# teensy_dev_board.net
KiCad netlist of a schematic drawn in EAGLE
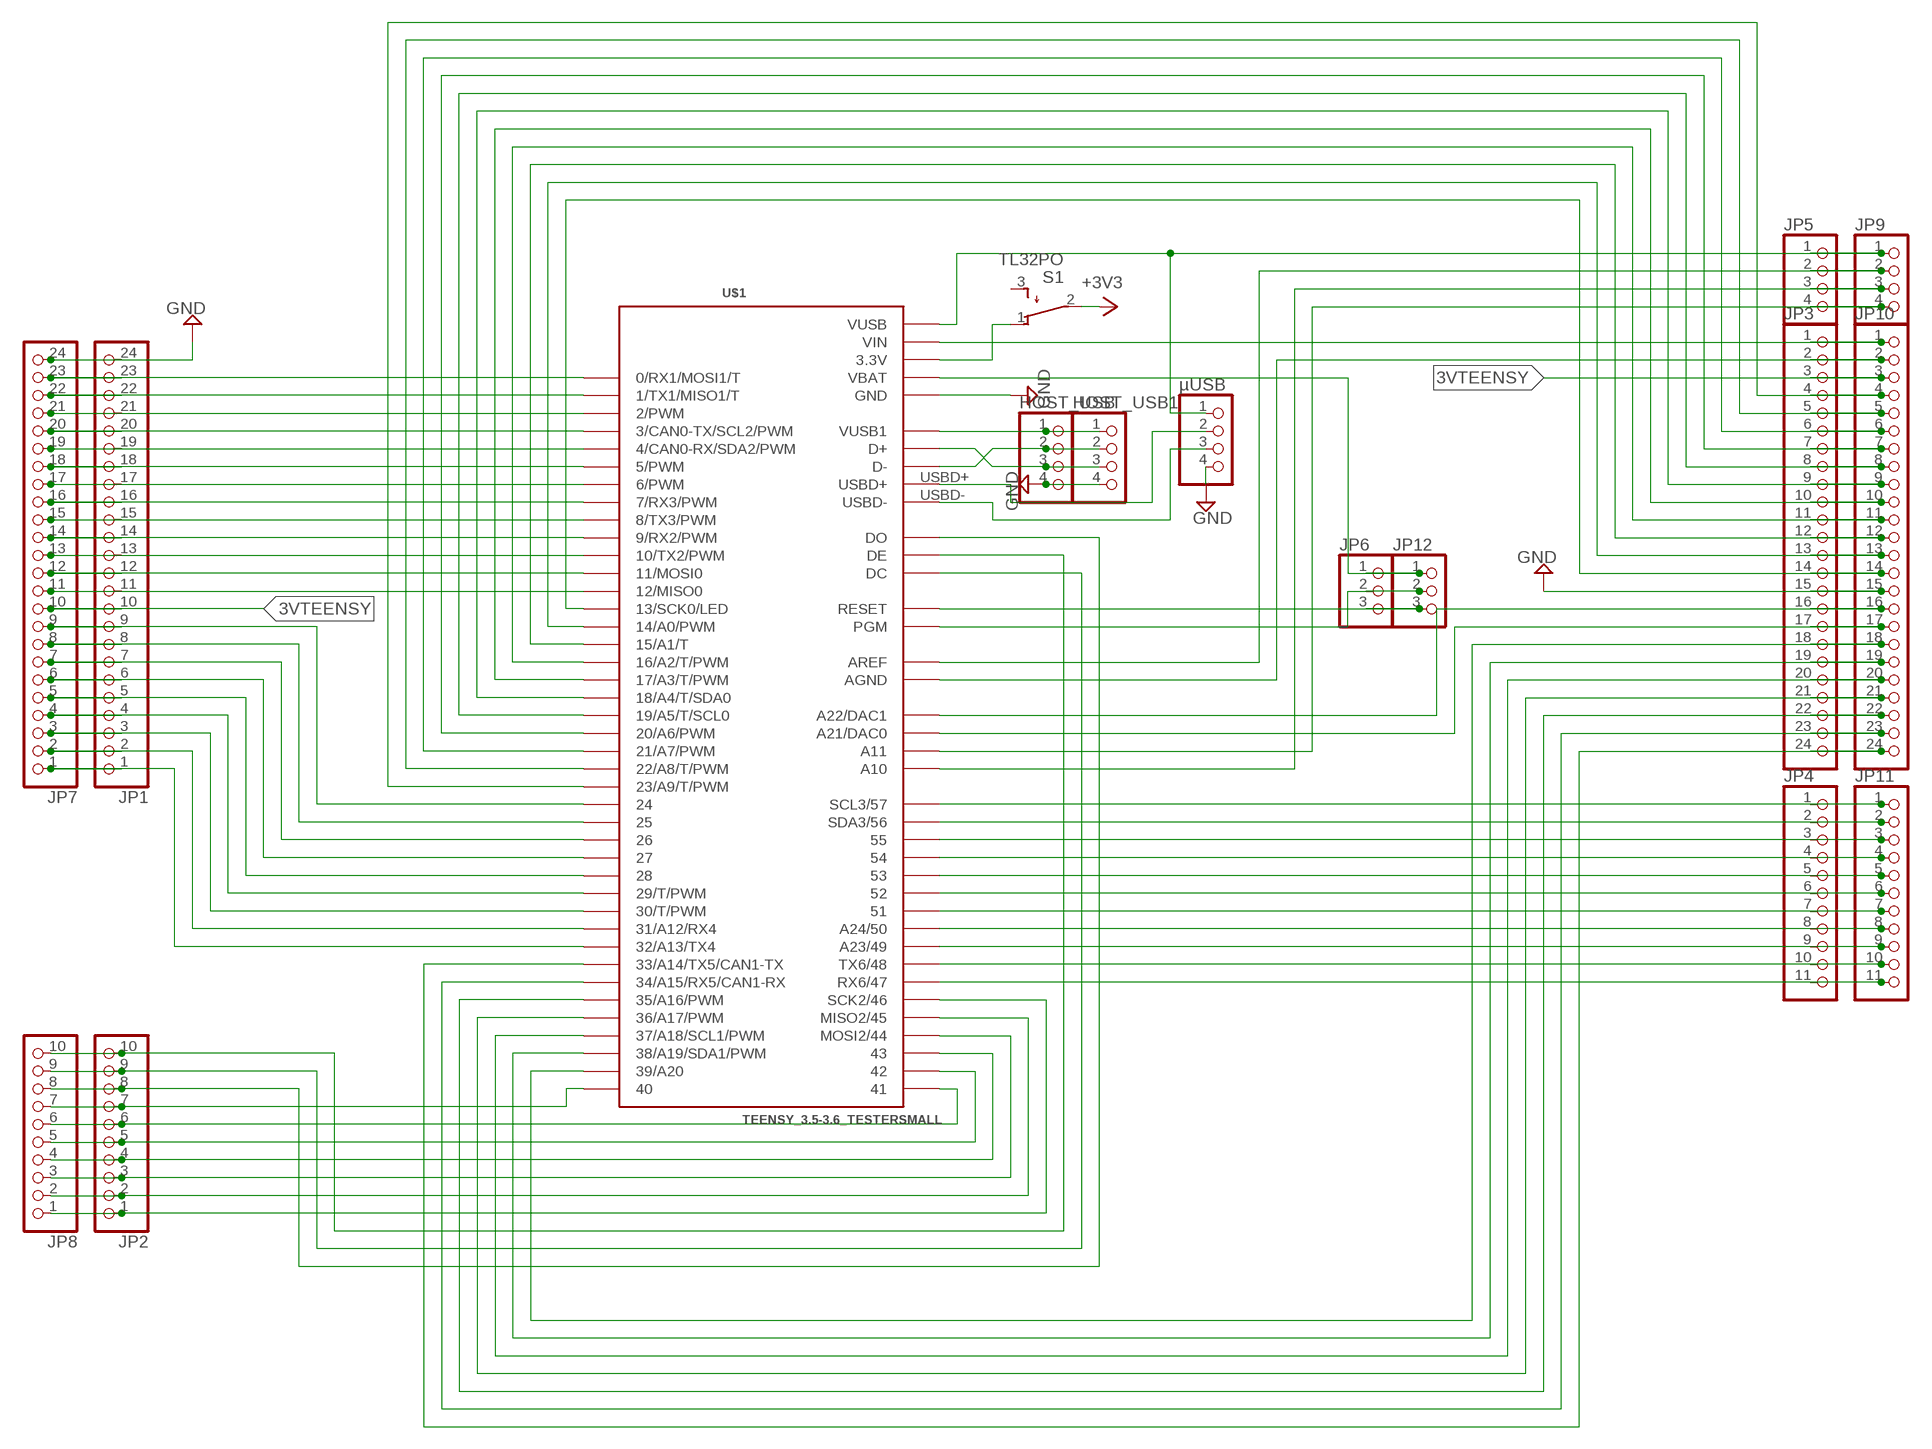
[diagram p0: schematic, sheet 1, part 1 of 2]
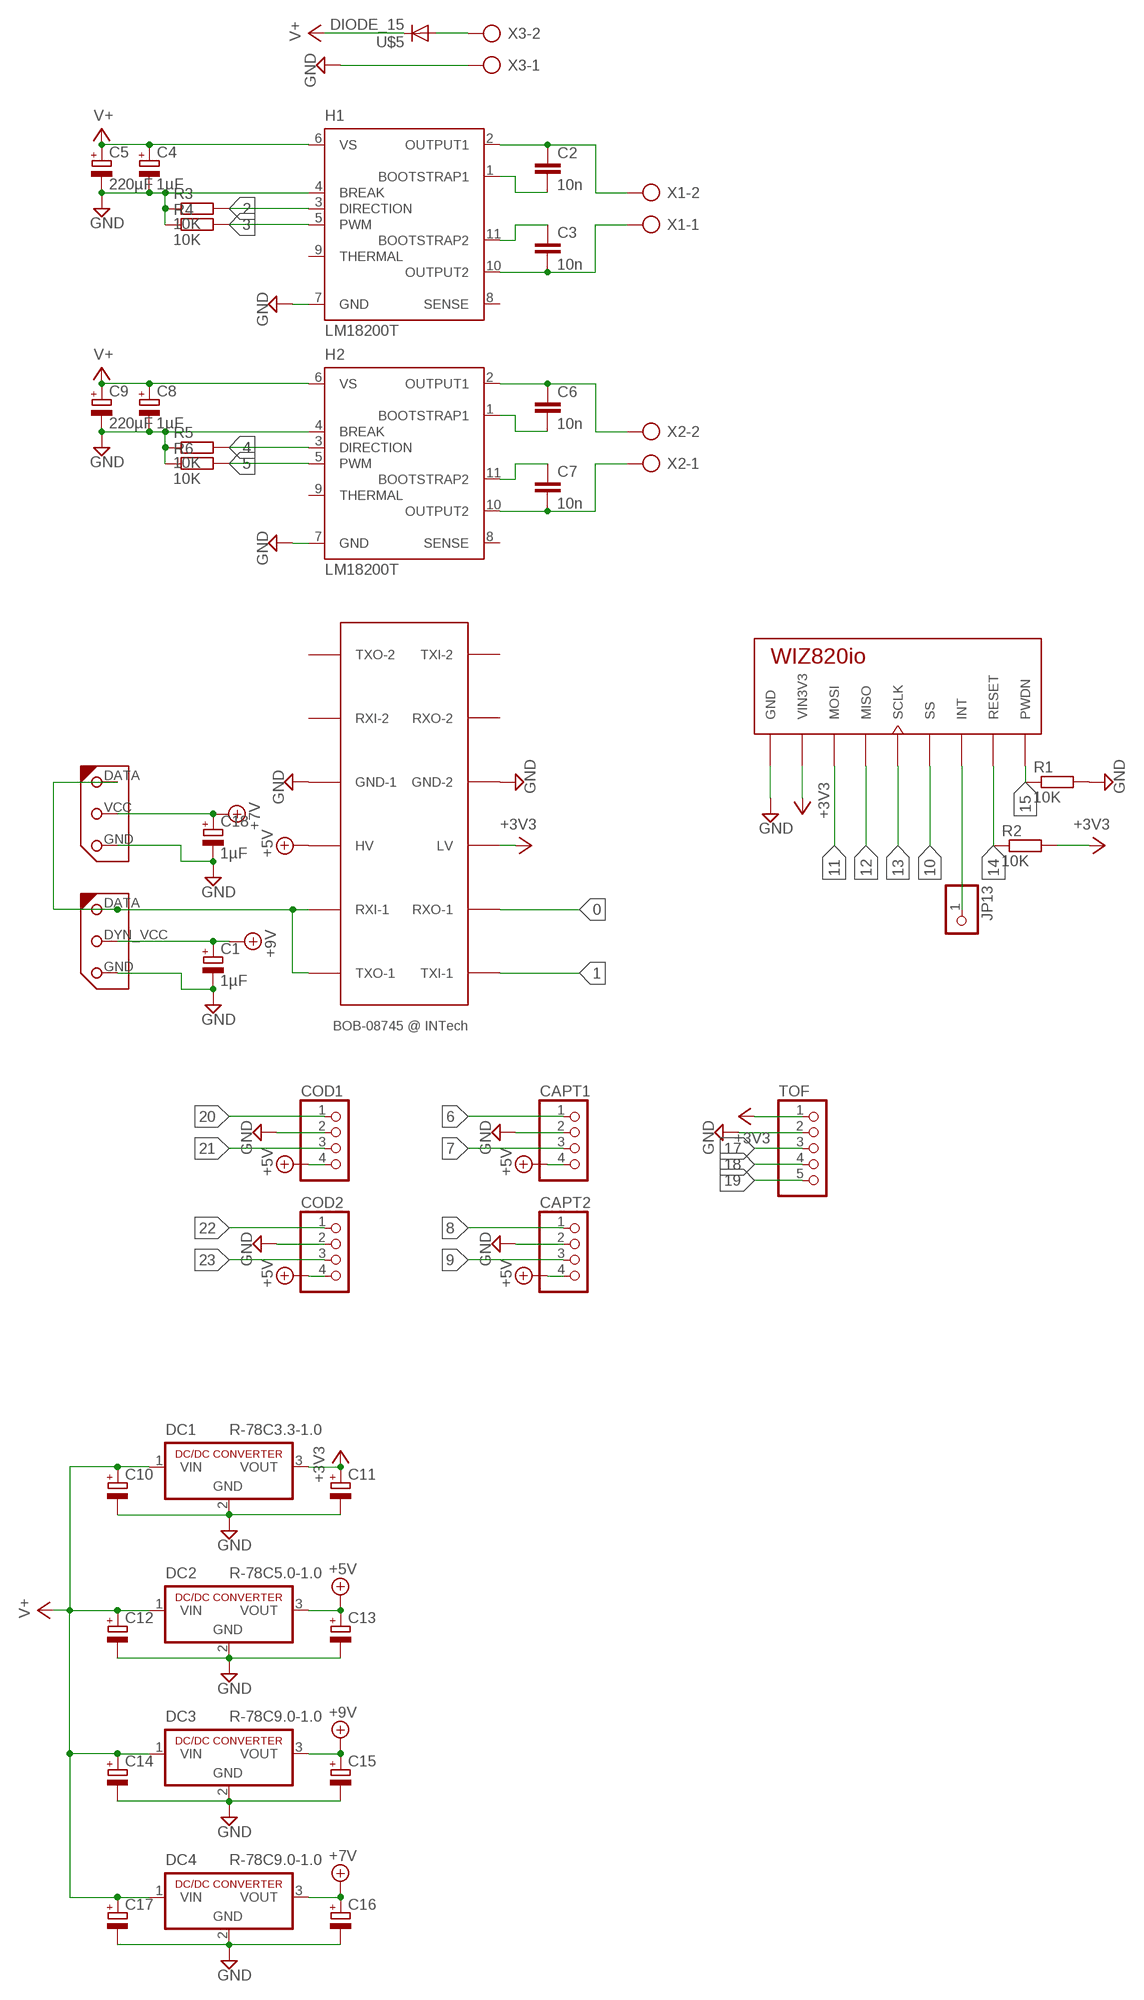
[diagram p1: schematic, sheet 1, part 2 of 2]

(export (version "E")
  (design (tool "Eeschema 10.0.6"))
  (components
    (comp (ref "C1")
      (value "1µF")
      (footprint "eagle-import:E2,5-6E")
      (libsource (lib "eagle-import") (part "CPOL-EUE2,5-6E"))
    )
    (comp (ref "C2")
      (value "10n")
      (footprint "eagle-import:C050-025X075")
      (libsource (lib "eagle-import") (part "C-EU050-025X075"))
    )
    (comp (ref "C3")
      (value "10n")
      (footprint "eagle-import:C050-025X075")
      (libsource (lib "eagle-import") (part "C-EU050-025X075"))
    )
    (comp (ref "C4")
      (value "1µF")
      (footprint "eagle-import:E2,5-7")
      (libsource (lib "eagle-import") (part "CPOL-EUE2.5-7"))
    )
    (comp (ref "C5")
      (value "220µF")
      (footprint "eagle-import:E2,5-7")
      (libsource (lib "eagle-import") (part "CPOL-EUE2.5-7"))
    )
    (comp (ref "C6")
      (value "10n")
      (footprint "eagle-import:C050-025X075")
      (libsource (lib "eagle-import") (part "C-EU050-025X075"))
    )
    (comp (ref "C7")
      (value "10n")
      (footprint "eagle-import:C050-025X075")
      (libsource (lib "eagle-import") (part "C-EU050-025X075"))
    )
    (comp (ref "C8")
      (value "1µF")
      (footprint "eagle-import:E2,5-7")
      (libsource (lib "eagle-import") (part "CPOL-EUE2.5-7"))
    )
    (comp (ref "C9")
      (value "220µF")
      (footprint "eagle-import:E2,5-7")
      (libsource (lib "eagle-import") (part "CPOL-EUE2.5-7"))
    )
    (comp (ref "C10")
      (value "CPOL-EUE2.5-6")
      (footprint "eagle-import:E2,5-6")
      (libsource (lib "eagle-import") (part "CPOL-EUE2.5-6"))
    )
    (comp (ref "C11")
      (value "CPOL-EUE2.5-6")
      (footprint "eagle-import:E2,5-6")
      (libsource (lib "eagle-import") (part "CPOL-EUE2.5-6"))
    )
    (comp (ref "C12")
      (value "CPOL-EUE2.5-6")
      (footprint "eagle-import:E2,5-6")
      (libsource (lib "eagle-import") (part "CPOL-EUE2.5-6"))
    )
    (comp (ref "C13")
      (value "CPOL-EUE2.5-6")
      (footprint "eagle-import:E2,5-6")
      (libsource (lib "eagle-import") (part "CPOL-EUE2.5-6"))
    )
    (comp (ref "C14")
      (value "CPOL-EUE2.5-6")
      (footprint "eagle-import:E2,5-6")
      (libsource (lib "eagle-import") (part "CPOL-EUE2.5-6"))
    )
    (comp (ref "C15")
      (value "CPOL-EUE2.5-6")
      (footprint "eagle-import:E2,5-6")
      (libsource (lib "eagle-import") (part "CPOL-EUE2.5-6"))
    )
    (comp (ref "C16")
      (value "CPOL-EUE2.5-6")
      (footprint "eagle-import:E2,5-6")
      (libsource (lib "eagle-import") (part "CPOL-EUE2.5-6"))
    )
    (comp (ref "C17")
      (value "CPOL-EUE2.5-6")
      (footprint "eagle-import:E2,5-6")
      (libsource (lib "eagle-import") (part "CPOL-EUE2.5-6"))
    )
    (comp (ref "C18")
      (value "1µF")
      (footprint "eagle-import:E2,5-6E")
      (libsource (lib "eagle-import") (part "CPOL-EUE2,5-6E"))
    )
    (comp (ref "CAPT1")
      (value "PINHD-1X4B")
      (footprint "eagle-import:1X04B")
      (libsource (lib "eagle-import") (part "PINHD-1X4B"))
    )
    (comp (ref "CAPT2")
      (value "PINHD-1X4B")
      (footprint "eagle-import:1X04B")
      (libsource (lib "eagle-import") (part "PINHD-1X4B"))
    )
    (comp (ref "COD1")
      (value "PINHD-1X4B")
      (footprint "eagle-import:1X04B")
      (libsource (lib "eagle-import") (part "PINHD-1X4B"))
    )
    (comp (ref "COD2")
      (value "PINHD-1X4B")
      (footprint "eagle-import:1X04B")
      (libsource (lib "eagle-import") (part "PINHD-1X4B"))
    )
    (comp (ref "DC1")
      (value "R-78C3.3-1.0")
      (footprint "eagle-import:SIP3")
      (libsource (lib "eagle-import") (part "R-78C-1.03.3"))
    )
    (comp (ref "DC2")
      (value "R-78C5.0-1.0")
      (footprint "eagle-import:SIP3")
      (libsource (lib "eagle-import") (part "R-78C-1.05.0"))
    )
    (comp (ref "DC3")
      (value "R-78C9.0-1.0")
      (footprint "eagle-import:SIP3")
      (libsource (lib "eagle-import") (part "R-78C-1.09.0"))
    )
    (comp (ref "DC4")
      (value "R-78C9.0-1.0")
      (footprint "eagle-import:SIP3")
      (libsource (lib "eagle-import") (part "R-78C-1.09.0"))
    )
    (comp (ref "H1")
      (value "LM18200T")
      (footprint "eagle-import:TO-220-11")
      (libsource (lib "eagle-import") (part "LM18200T"))
    )
    (comp (ref "H2")
      (value "LM18200T")
      (footprint "eagle-import:TO-220-11")
      (libsource (lib "eagle-import") (part "LM18200T"))
    )
    (comp (ref "HOST_USB")
      (value "PINHD-1X4")
      (footprint "eagle-import:1X04")
      (libsource (lib "eagle-import") (part "PINHD-1X4"))
    )
    (comp (ref "HOST_USB1")
      (value "PINHD-1X4")
      (footprint "eagle-import:1X04")
      (libsource (lib "eagle-import") (part "PINHD-1X4"))
    )
    (comp (ref "JP1")
      (value "PINHD-1X24")
      (footprint "eagle-import:1X24")
      (libsource (lib "eagle-import") (part "PINHD-1X24"))
    )
    (comp (ref "JP2")
      (value "PINHD-1X10")
      (footprint "eagle-import:1X10")
      (libsource (lib "eagle-import") (part "PINHD-1X10"))
    )
    (comp (ref "JP3")
      (value "PINHD-1X24")
      (footprint "eagle-import:1X24")
      (libsource (lib "eagle-import") (part "PINHD-1X24"))
    )
    (comp (ref "JP4")
      (value "PINHD-1X11")
      (footprint "eagle-import:1X11")
      (libsource (lib "eagle-import") (part "PINHD-1X11"))
    )
    (comp (ref "JP5")
      (value "PINHD-1X4")
      (footprint "eagle-import:1X04")
      (libsource (lib "eagle-import") (part "PINHD-1X4"))
    )
    (comp (ref "JP6")
      (value "PINHD-1X3")
      (footprint "eagle-import:1X03")
      (libsource (lib "eagle-import") (part "PINHD-1X3"))
    )
    (comp (ref "JP7")
      (value "PINHD-1X24")
      (footprint "eagle-import:1X24")
      (libsource (lib "eagle-import") (part "PINHD-1X24"))
    )
    (comp (ref "JP8")
      (value "PINHD-1X10")
      (footprint "eagle-import:1X10")
      (libsource (lib "eagle-import") (part "PINHD-1X10"))
    )
    (comp (ref "JP9")
      (value "PINHD-1X4")
      (footprint "eagle-import:1X04")
      (libsource (lib "eagle-import") (part "PINHD-1X4"))
    )
    (comp (ref "JP10")
      (value "PINHD-1X24")
      (footprint "eagle-import:1X24")
      (libsource (lib "eagle-import") (part "PINHD-1X24"))
    )
    (comp (ref "JP11")
      (value "PINHD-1X11")
      (footprint "eagle-import:1X11")
      (libsource (lib "eagle-import") (part "PINHD-1X11"))
    )
    (comp (ref "JP12")
      (value "PINHD-1X3")
      (footprint "eagle-import:1X03")
      (libsource (lib "eagle-import") (part "PINHD-1X3"))
    )
    (comp (ref "JP13")
      (value "PINHD-1X1")
      (footprint "eagle-import:1X01")
      (libsource (lib "eagle-import") (part "PINHD-1X1"))
    )
    (comp (ref "R1")
      (value "10K")
      (footprint "eagle-import:0204_7")
      (libsource (lib "eagle-import") (part "R-EU_0204/7"))
    )
    (comp (ref "R2")
      (value "10K")
      (footprint "eagle-import:0204_7")
      (libsource (lib "eagle-import") (part "R-EU_0204/7"))
    )
    (comp (ref "R3")
      (value "10K")
      (footprint "eagle-import:0204_7")
      (libsource (lib "eagle-import") (part "R-EU_0204/7"))
    )
    (comp (ref "R4")
      (value "10K")
      (footprint "eagle-import:0204_7")
      (libsource (lib "eagle-import") (part "R-EU_0204/7"))
    )
    (comp (ref "R5")
      (value "10K")
      (footprint "eagle-import:0204_7")
      (libsource (lib "eagle-import") (part "R-EU_0204/7"))
    )
    (comp (ref "R6")
      (value "10K")
      (footprint "eagle-import:0204_7")
      (libsource (lib "eagle-import") (part "R-EU_0204/7"))
    )
    (comp (ref "S1")
      (value "TL32PO")
      (footprint "eagle-import:TL3XPO")
      (libsource (lib "eagle-import") (part "TL32PO"))
    )
    (comp (ref "TOF")
      (value "PINHD-1X5B")
      (footprint "eagle-import:1X05B")
      (libsource (lib "eagle-import") (part "PINHD-1X5B"))
    )
    (comp (ref "U$1")
      (value "TEENSY_3.5-3.6_TESTERSMALL")
      (footprint "eagle-import:TEENSY_3.5-3.6_TESTER_SMALL")
      (libsource (lib "eagle-import") (part "TEENSY_3.5-3.6_TESTERSMALL"))
    )
    (comp (ref "U$2")
      (value "BOB-08745")
      (footprint "eagle-import:BOB-08745")
      (libsource (lib "eagle-import") (part "BOB-08745"))
    )
    (comp (ref "U$3")
      (value "DYNAMIXEL-1X03AX")
      (footprint "eagle-import:DYNAMIXEL_AX_1X03")
      (libsource (lib "eagle-import") (part "DYNAMIXEL-1X03AX"))
    )
    (comp (ref "U$4")
      (value "WIZ820IO")
      (footprint "eagle-import:WIZ820")
      (libsource (lib "eagle-import") (part "WIZ820IO"))
    )
    (comp (ref "U$5")
      (value "DIODE_15")
      (footprint "eagle-import:DO201-15")
      (libsource (lib "eagle-import") (part "DIODE_15"))
    )
    (comp (ref "U$6")
      (value "DYNAMIXEL-1X03XL")
      (footprint "eagle-import:DYNAMIXEL_XL_1X03")
      (libsource (lib "eagle-import") (part "DYNAMIXEL-1X03XL"))
    )
    (comp (ref "X1")
      (value "AK300/2")
      (footprint "eagle-import:AK300_2")
      (libsource (lib "eagle-import") (part "AK300/2"))
    )
    (comp (ref "X2")
      (value "AK300/2")
      (footprint "eagle-import:AK300_2")
      (libsource (lib "eagle-import") (part "AK300/2"))
    )
    (comp (ref "X3")
      (value "AK300/2")
      (footprint "eagle-import:AK300_2")
      (libsource (lib "eagle-import") (part "AK300/2"))
    )
    (comp (ref "µUSB")
      (value "PINHD-1X4")
      (footprint "eagle-import:1X04")
      (libsource (lib "eagle-import") (part "PINHD-1X4"))
    )
  )
  (nets
    (net (code "1") (name "+3V3") (class "Default")
      (node (ref "C11") (pin "+") (pinfunction "+_+") (pintype "passive"))
      (node (ref "DC1") (pin "3") (pinfunction "VOUT_3") (pintype "passive"))
      (node (ref "R2") (pin "2") (pinfunction "2_2") (pintype "passive"))
      (node (ref "S1") (pin "2") (pinfunction "P_2") (pintype "passive"))
      (node (ref "TOF") (pin "1") (pinfunction "1_1") (pintype "passive"))
      (node (ref "U$2") (pin "LV") (pinfunction "LV_LV") (pintype "bidirectional"))
      (node (ref "U$4") (pin "VIN1") (pinfunction "VIN3V3_VIN1") (pintype "power_in"))
      (node (ref "U$4") (pin "VIN2") (pinfunction "VIN3V3_VIN2") (pintype "power_in"))
    )
    (net (code "2") (name "+5V") (class "Default")
      (node (ref "C13") (pin "+") (pinfunction "+_+") (pintype "passive"))
      (node (ref "CAPT1") (pin "4") (pinfunction "4_4") (pintype "passive"))
      (node (ref "CAPT2") (pin "4") (pinfunction "4_4") (pintype "passive"))
      (node (ref "COD1") (pin "4") (pinfunction "4_4") (pintype "passive"))
      (node (ref "COD2") (pin "4") (pinfunction "4_4") (pintype "passive"))
      (node (ref "DC2") (pin "3") (pinfunction "VOUT_3") (pintype "passive"))
      (node (ref "U$2") (pin "HV") (pinfunction "HV_HV") (pintype "bidirectional"))
    )
    (net (code "3") (name "+7V") (class "Default")
      (node (ref "C16") (pin "+") (pinfunction "+_+") (pintype "passive"))
      (node (ref "C18") (pin "+") (pinfunction "+_+") (pintype "passive"))
      (node (ref "DC4") (pin "3") (pinfunction "VOUT_3") (pintype "passive"))
      (node (ref "U$6") (pin "VCC") (pinfunction "DYN_VCC_VCC") (pintype "power_in"))
    )
    (net (code "4") (name "+9V") (class "Default")
      (node (ref "C1") (pin "+") (pinfunction "+_+") (pintype "passive"))
      (node (ref "C15") (pin "+") (pinfunction "+_+") (pintype "passive"))
      (node (ref "DC3") (pin "3") (pinfunction "VOUT_3") (pintype "passive"))
      (node (ref "U$3") (pin "DYN_VCC") (pinfunction "DYN_VCC_DYN_VCC") (pintype "power_in"))
    )
    (net (code "5") (name "0") (class "Default")
      (node (ref "JP1") (pin "23") (pinfunction "23_23") (pintype "passive"))
      (node (ref "JP7") (pin "23") (pinfunction "23_23") (pintype "passive"))
      (node (ref "U$1") (pin "0") (pinfunction "0/RX1/MOSI1/T_0") (pintype "bidirectional"))
      (node (ref "U$2") (pin "RXO-1") (pinfunction "RXO-1_RXO-1") (pintype "bidirectional"))
    )
    (net (code "6") (name "1") (class "Default")
      (node (ref "JP1") (pin "22") (pinfunction "22_22") (pintype "passive"))
      (node (ref "JP7") (pin "22") (pinfunction "22_22") (pintype "passive"))
      (node (ref "U$1") (pin "1") (pinfunction "1/TX1/MISO1/T_1") (pintype "bidirectional"))
      (node (ref "U$2") (pin "TXI-1") (pinfunction "TXI-1_TXI-1") (pintype "bidirectional"))
    )
    (net (code "7") (name "2") (class "Default")
      (node (ref "H1") (pin "3") (pinfunction "DIRECTION_3") (pintype "input"))
      (node (ref "JP1") (pin "21") (pinfunction "21_21") (pintype "passive"))
      (node (ref "JP7") (pin "21") (pinfunction "21_21") (pintype "passive"))
      (node (ref "R3") (pin "2") (pinfunction "2_2") (pintype "passive"))
      (node (ref "U$1") (pin "2") (pinfunction "2/PWM_2") (pintype "bidirectional"))
    )
    (net (code "8") (name "3") (class "Default")
      (node (ref "H1") (pin "5") (pinfunction "PWM_5") (pintype "input"))
      (node (ref "JP1") (pin "20") (pinfunction "20_20") (pintype "passive"))
      (node (ref "JP7") (pin "20") (pinfunction "20_20") (pintype "passive"))
      (node (ref "R4") (pin "2") (pinfunction "2_2") (pintype "passive"))
      (node (ref "U$1") (pin "3") (pinfunction "3/CAN0-TX/SCL2/PWM_3") (pintype "bidirectional"))
    )
    (net (code "9") (name "3VTEENSY") (class "Default")
      (node (ref "JP1") (pin "10") (pinfunction "10_10") (pintype "passive"))
      (node (ref "JP10") (pin "3") (pinfunction "3_3") (pintype "passive"))
      (node (ref "JP3") (pin "3") (pinfunction "3_3") (pintype "passive"))
      (node (ref "JP7") (pin "10") (pinfunction "10_10") (pintype "passive"))
      (node (ref "S1") (pin "1") (pinfunction "O_1") (pintype "passive"))
      (node (ref "U$1") (pin "3.3V") (pinfunction "3.3V_3.3V") (pintype "power_in"))
      (node (ref "U$1") (pin "3.3V2") (pinfunction "3.3V_3.3V2") (pintype "power_in"))
      (node (ref "U$1") (pin "3.3V3") (pinfunction "3.3V_3.3V3") (pintype "power_in"))
      (node (ref "U$1") (pin "3.3V4") (pinfunction "3.3V_3.3V4") (pintype "power_in"))
    )
    (net (code "10") (name "4") (class "Default")
      (node (ref "H2") (pin "3") (pinfunction "DIRECTION_3") (pintype "input"))
      (node (ref "JP1") (pin "19") (pinfunction "19_19") (pintype "passive"))
      (node (ref "JP7") (pin "19") (pinfunction "19_19") (pintype "passive"))
      (node (ref "R5") (pin "2") (pinfunction "2_2") (pintype "passive"))
      (node (ref "U$1") (pin "4") (pinfunction "4/CAN0-RX/SDA2/PWM_4") (pintype "bidirectional"))
    )
    (net (code "11") (name "5") (class "Default")
      (node (ref "H2") (pin "5") (pinfunction "PWM_5") (pintype "input"))
      (node (ref "JP1") (pin "18") (pinfunction "18_18") (pintype "passive"))
      (node (ref "JP7") (pin "18") (pinfunction "18_18") (pintype "passive"))
      (node (ref "R6") (pin "2") (pinfunction "2_2") (pintype "passive"))
      (node (ref "U$1") (pin "5") (pinfunction "5/PWM_5") (pintype "bidirectional"))
    )
    (net (code "12") (name "6") (class "Default")
      (node (ref "CAPT1") (pin "1") (pinfunction "1_1") (pintype "passive"))
      (node (ref "JP1") (pin "17") (pinfunction "17_17") (pintype "passive"))
      (node (ref "JP7") (pin "17") (pinfunction "17_17") (pintype "passive"))
      (node (ref "U$1") (pin "6") (pinfunction "6/PWM_6") (pintype "bidirectional"))
    )
    (net (code "13") (name "7") (class "Default")
      (node (ref "CAPT1") (pin "3") (pinfunction "3_3") (pintype "passive"))
      (node (ref "JP1") (pin "16") (pinfunction "16_16") (pintype "passive"))
      (node (ref "JP7") (pin "16") (pinfunction "16_16") (pintype "passive"))
      (node (ref "U$1") (pin "7") (pinfunction "7/RX3/PWM_7") (pintype "bidirectional"))
    )
    (net (code "14") (name "8") (class "Default")
      (node (ref "CAPT2") (pin "1") (pinfunction "1_1") (pintype "passive"))
      (node (ref "JP1") (pin "15") (pinfunction "15_15") (pintype "passive"))
      (node (ref "JP7") (pin "15") (pinfunction "15_15") (pintype "passive"))
      (node (ref "U$1") (pin "8") (pinfunction "8/TX3/PWM_8") (pintype "bidirectional"))
    )
    (net (code "15") (name "9") (class "Default")
      (node (ref "CAPT2") (pin "3") (pinfunction "3_3") (pintype "passive"))
      (node (ref "JP1") (pin "14") (pinfunction "14_14") (pintype "passive"))
      (node (ref "JP7") (pin "14") (pinfunction "14_14") (pintype "passive"))
      (node (ref "U$1") (pin "9") (pinfunction "9/RX2/PWM_9") (pintype "bidirectional"))
    )
    (net (code "16") (name "10") (class "Default")
      (node (ref "JP1") (pin "13") (pinfunction "13_13") (pintype "passive"))
      (node (ref "JP7") (pin "13") (pinfunction "13_13") (pintype "passive"))
      (node (ref "U$1") (pin "10") (pinfunction "10/TX2/PWM_10") (pintype "bidirectional"))
      (node (ref "U$4") (pin "SS") (pinfunction "SS_SS") (pintype "bidirectional"))
    )
    (net (code "17") (name "11") (class "Default")
      (node (ref "JP1") (pin "12") (pinfunction "12_12") (pintype "passive"))
      (node (ref "JP7") (pin "12") (pinfunction "12_12") (pintype "passive"))
      (node (ref "U$1") (pin "11") (pinfunction "11/MOSI0_11") (pintype "bidirectional"))
      (node (ref "U$4") (pin "MOSI") (pinfunction "MOSI_MOSI") (pintype "bidirectional"))
    )
    (net (code "18") (name "12") (class "Default")
      (node (ref "JP1") (pin "11") (pinfunction "11_11") (pintype "passive"))
      (node (ref "JP7") (pin "11") (pinfunction "11_11") (pintype "passive"))
      (node (ref "U$1") (pin "12") (pinfunction "12/MISO0_12") (pintype "bidirectional"))
      (node (ref "U$4") (pin "MISO") (pinfunction "MISO_MISO") (pintype "bidirectional"))
    )
    (net (code "19") (name "13") (class "Default")
      (node (ref "JP10") (pin "14") (pinfunction "14_14") (pintype "passive"))
      (node (ref "JP3") (pin "14") (pinfunction "14_14") (pintype "passive"))
      (node (ref "U$1") (pin "13") (pinfunction "13/SCK0/LED_13") (pintype "bidirectional"))
      (node (ref "U$4") (pin "SCLK") (pinfunction "SCLK_SCLK") (pintype "bidirectional"))
    )
    (net (code "20") (name "14") (class "Default")
      (node (ref "JP10") (pin "13") (pinfunction "13_13") (pintype "passive"))
      (node (ref "JP3") (pin "13") (pinfunction "13_13") (pintype "passive"))
      (node (ref "R2") (pin "1") (pinfunction "1_1") (pintype "passive"))
      (node (ref "U$1") (pin "14/A0") (pinfunction "14/A0/PWM_14/A0") (pintype "bidirectional"))
      (node (ref "U$4") (pin "RESET") (pinfunction "RESET_RESET") (pintype "bidirectional"))
    )
    (net (code "21") (name "15") (class "Default")
      (node (ref "JP10") (pin "12") (pinfunction "12_12") (pintype "passive"))
      (node (ref "JP3") (pin "12") (pinfunction "12_12") (pintype "passive"))
      (node (ref "R1") (pin "1") (pinfunction "1_1") (pintype "passive"))
      (node (ref "U$1") (pin "15/A1") (pinfunction "15/A1/T_15/A1") (pintype "bidirectional"))
      (node (ref "U$4") (pin "PWDN") (pinfunction "PWDN_PWDN") (pintype "bidirectional"))
    )
    (net (code "22") (name "17") (class "Default")
      (node (ref "JP10") (pin "10") (pinfunction "10_10") (pintype "passive"))
      (node (ref "JP3") (pin "10") (pinfunction "10_10") (pintype "passive"))
      (node (ref "TOF") (pin "3") (pinfunction "3_3") (pintype "passive"))
      (node (ref "U$1") (pin "17/A3") (pinfunction "17/A3/T/PWM_17/A3") (pintype "bidirectional"))
    )
    (net (code "23") (name "18") (class "Default")
      (node (ref "JP10") (pin "9") (pinfunction "9_9") (pintype "passive"))
      (node (ref "JP3") (pin "9") (pinfunction "9_9") (pintype "passive"))
      (node (ref "TOF") (pin "4") (pinfunction "4_4") (pintype "passive"))
      (node (ref "U$1") (pin "18/A4") (pinfunction "18/A4/T/SDA0_18/A4") (pintype "bidirectional"))
    )
    (net (code "24") (name "19") (class "Default")
      (node (ref "JP10") (pin "8") (pinfunction "8_8") (pintype "passive"))
      (node (ref "JP3") (pin "8") (pinfunction "8_8") (pintype "passive"))
      (node (ref "TOF") (pin "5") (pinfunction "5_5") (pintype "passive"))
      (node (ref "U$1") (pin "19/A5") (pinfunction "19/A5/T/SCL0_19/A5") (pintype "bidirectional"))
    )
    (net (code "25") (name "20") (class "Default")
      (node (ref "COD1") (pin "1") (pinfunction "1_1") (pintype "passive"))
      (node (ref "JP10") (pin "7") (pinfunction "7_7") (pintype "passive"))
      (node (ref "JP3") (pin "7") (pinfunction "7_7") (pintype "passive"))
      (node (ref "U$1") (pin "20/A6") (pinfunction "20/A6/PWM_20/A6") (pintype "bidirectional"))
    )
    (net (code "26") (name "21") (class "Default")
      (node (ref "COD1") (pin "3") (pinfunction "3_3") (pintype "passive"))
      (node (ref "JP10") (pin "6") (pinfunction "6_6") (pintype "passive"))
      (node (ref "JP3") (pin "6") (pinfunction "6_6") (pintype "passive"))
      (node (ref "U$1") (pin "21/A7") (pinfunction "21/A7/PWM_21/A7") (pintype "bidirectional"))
    )
    (net (code "27") (name "22") (class "Default")
      (node (ref "COD2") (pin "1") (pinfunction "1_1") (pintype "passive"))
      (node (ref "JP10") (pin "5") (pinfunction "5_5") (pintype "passive"))
      (node (ref "JP3") (pin "5") (pinfunction "5_5") (pintype "passive"))
      (node (ref "U$1") (pin "22/A8") (pinfunction "22/A8/T/PWM_22/A8") (pintype "bidirectional"))
    )
    (net (code "28") (name "23") (class "Default")
      (node (ref "COD2") (pin "3") (pinfunction "3_3") (pintype "passive"))
      (node (ref "JP10") (pin "4") (pinfunction "4_4") (pintype "passive"))
      (node (ref "JP3") (pin "4") (pinfunction "4_4") (pintype "passive"))
      (node (ref "U$1") (pin "23/A9") (pinfunction "23/A9/T/PWM_23/A9") (pintype "bidirectional"))
    )
    (net (code "29") (name "GND") (class "Default")
      (node (ref "C1") (pin "-") (pinfunction "-_-") (pintype "passive"))
      (node (ref "C10") (pin "-") (pinfunction "-_-") (pintype "passive"))
      (node (ref "C11") (pin "-") (pinfunction "-_-") (pintype "passive"))
      (node (ref "C12") (pin "-") (pinfunction "-_-") (pintype "passive"))
      (node (ref "C13") (pin "-") (pinfunction "-_-") (pintype "passive"))
      (node (ref "C14") (pin "-") (pinfunction "-_-") (pintype "passive"))
      (node (ref "C15") (pin "-") (pinfunction "-_-") (pintype "passive"))
      (node (ref "C16") (pin "-") (pinfunction "-_-") (pintype "passive"))
      (node (ref "C17") (pin "-") (pinfunction "-_-") (pintype "passive"))
      (node (ref "C18") (pin "-") (pinfunction "-_-") (pintype "passive"))
      (node (ref "C4") (pin "-") (pinfunction "-_-") (pintype "passive"))
      (node (ref "C5") (pin "-") (pinfunction "-_-") (pintype "passive"))
      (node (ref "C8") (pin "-") (pinfunction "-_-") (pintype "passive"))
      (node (ref "C9") (pin "-") (pinfunction "-_-") (pintype "passive"))
      (node (ref "CAPT1") (pin "2") (pinfunction "2_2") (pintype "passive"))
      (node (ref "CAPT2") (pin "2") (pinfunction "2_2") (pintype "passive"))
      (node (ref "COD1") (pin "2") (pinfunction "2_2") (pintype "passive"))
      (node (ref "COD2") (pin "2") (pinfunction "2_2") (pintype "passive"))
      (node (ref "DC1") (pin "2") (pinfunction "GND_2") (pintype "passive"))
      (node (ref "DC2") (pin "2") (pinfunction "GND_2") (pintype "passive"))
      (node (ref "DC3") (pin "2") (pinfunction "GND_2") (pintype "passive"))
      (node (ref "DC4") (pin "2") (pinfunction "GND_2") (pintype "passive"))
      (node (ref "H1") (pin "4") (pinfunction "BREAK_4") (pintype "input"))
      (node (ref "H1") (pin "7") (pinfunction "GND_7") (pintype "power_in"))
      (node (ref "H2") (pin "4") (pinfunction "BREAK_4") (pintype "input"))
      (node (ref "H2") (pin "7") (pinfunction "GND_7") (pintype "power_in"))
      (node (ref "HOST_USB") (pin "4") (pinfunction "4_4") (pintype "passive"))
      (node (ref "HOST_USB1") (pin "4") (pinfunction "4_4") (pintype "passive"))
      (node (ref "JP1") (pin "24") (pinfunction "24_24") (pintype "passive"))
      (node (ref "JP10") (pin "15") (pinfunction "15_15") (pintype "passive"))
      (node (ref "JP3") (pin "15") (pinfunction "15_15") (pintype "passive"))
      (node (ref "JP7") (pin "24") (pinfunction "24_24") (pintype "passive"))
      (node (ref "R1") (pin "2") (pinfunction "2_2") (pintype "passive"))
      (node (ref "R3") (pin "1") (pinfunction "1_1") (pintype "passive"))
      (node (ref "R4") (pin "1") (pinfunction "1_1") (pintype "passive"))
      (node (ref "R5") (pin "1") (pinfunction "1_1") (pintype "passive"))
      (node (ref "R6") (pin "1") (pinfunction "1_1") (pintype "passive"))
      (node (ref "TOF") (pin "2") (pinfunction "2_2") (pintype "passive"))
      (node (ref "U$1") (pin "GND") (pinfunction "GND_GND") (pintype "power_in"))
      (node (ref "U$1") (pin "GND1") (pinfunction "GND_GND1") (pintype "power_in"))
      (node (ref "U$1") (pin "GND2") (pinfunction "GND_GND2") (pintype "power_in"))
      (node (ref "U$1") (pin "GND3") (pinfunction "GND_GND3") (pintype "power_in"))
      (node (ref "U$1") (pin "GND4") (pinfunction "GND_GND4") (pintype "power_in"))
      (node (ref "U$1") (pin "GND5") (pinfunction "GND_GND5") (pintype "power_in"))
      (node (ref "U$1") (pin "GND6") (pinfunction "GND_GND6") (pintype "power_in"))
      (node (ref "U$2") (pin "GND-1") (pinfunction "GND-1_GND-1") (pintype "bidirectional"))
      (node (ref "U$2") (pin "GND-2") (pinfunction "GND-2_GND-2") (pintype "bidirectional"))
      (node (ref "U$3") (pin "GND") (pinfunction "GND_GND") (pintype "power_in"))
      (node (ref "U$4") (pin "GND1") (pinfunction "GND_GND1") (pintype "power_in"))
      (node (ref "U$4") (pin "GND2") (pinfunction "GND_GND2") (pintype "power_in"))
      (node (ref "U$4") (pin "GND3") (pinfunction "GND_GND3") (pintype "power_in"))
      (node (ref "U$6") (pin "GND") (pinfunction "GND_GND") (pintype "power_in"))
      (node (ref "X3") (pin "1") (pinfunction "KL_1") (pintype "passive"))
      (node (ref "µUSB") (pin "4") (pinfunction "4_4") (pintype "passive"))
    )
    (net (code "30") (name "Net-(H1-BOOTSTRAP1)") (class "Default")
      (node (ref "C2") (pin "2") (pinfunction "2_2") (pintype "passive"))
      (node (ref "H1") (pin "1") (pinfunction "BOOTSTRAP1_1") (pintype "input"))
    )
    (net (code "31") (name "Net-(H1-BOOTSTRAP2)") (class "Default")
      (node (ref "C3") (pin "1") (pinfunction "1_1") (pintype "passive"))
      (node (ref "H1") (pin "11") (pinfunction "BOOTSTRAP2_11") (pintype "input"))
    )
    (net (code "32") (name "Net-(H1-OUTPUT1)") (class "Default")
      (node (ref "C2") (pin "1") (pinfunction "1_1") (pintype "passive"))
      (node (ref "H1") (pin "2") (pinfunction "OUTPUT1_2") (pintype "output"))
      (node (ref "X1") (pin "2") (pinfunction "KL_2") (pintype "passive"))
    )
    (net (code "33") (name "Net-(H1-OUTPUT2)") (class "Default")
      (node (ref "C3") (pin "2") (pinfunction "2_2") (pintype "passive"))
      (node (ref "H1") (pin "10") (pinfunction "OUTPUT2_10") (pintype "output"))
      (node (ref "X1") (pin "1") (pinfunction "KL_1") (pintype "passive"))
    )
    (net (code "34") (name "Net-(H2-BOOTSTRAP1)") (class "Default")
      (node (ref "C6") (pin "2") (pinfunction "2_2") (pintype "passive"))
      (node (ref "H2") (pin "1") (pinfunction "BOOTSTRAP1_1") (pintype "input"))
    )
    (net (code "35") (name "Net-(H2-BOOTSTRAP2)") (class "Default")
      (node (ref "C7") (pin "1") (pinfunction "1_1") (pintype "passive"))
      (node (ref "H2") (pin "11") (pinfunction "BOOTSTRAP2_11") (pintype "input"))
    )
    (net (code "36") (name "Net-(H2-OUTPUT1)") (class "Default")
      (node (ref "C6") (pin "1") (pinfunction "1_1") (pintype "passive"))
      (node (ref "H2") (pin "2") (pinfunction "OUTPUT1_2") (pintype "output"))
      (node (ref "X2") (pin "2") (pinfunction "KL_2") (pintype "passive"))
    )
    (net (code "37") (name "Net-(H2-OUTPUT2)") (class "Default")
      (node (ref "C7") (pin "2") (pinfunction "2_2") (pintype "passive"))
      (node (ref "H2") (pin "10") (pinfunction "OUTPUT2_10") (pintype "output"))
      (node (ref "X2") (pin "1") (pinfunction "KL_1") (pintype "passive"))
    )
    (net (code "38") (name "Net-(HOST_USB-Pad1)") (class "Default")
      (node (ref "HOST_USB") (pin "1") (pinfunction "1_1") (pintype "passive"))
      (node (ref "HOST_USB1") (pin "1") (pinfunction "1_1") (pintype "passive"))
      (node (ref "U$1") (pin "VUSB1") (pinfunction "VUSB1_VUSB1") (pintype "power_in"))
    )
    (net (code "39") (name "Net-(HOST_USB-Pad2)") (class "Default")
      (node (ref "HOST_USB") (pin "2") (pinfunction "2_2") (pintype "passive"))
      (node (ref "HOST_USB1") (pin "2") (pinfunction "2_2") (pintype "passive"))
      (node (ref "U$1") (pin "D-") (pinfunction "D-_D-") (pintype "bidirectional"))
    )
    (net (code "40") (name "Net-(HOST_USB-Pad3)") (class "Default")
      (node (ref "HOST_USB") (pin "3") (pinfunction "3_3") (pintype "passive"))
      (node (ref "HOST_USB1") (pin "3") (pinfunction "3_3") (pintype "passive"))
      (node (ref "U$1") (pin "D+") (pinfunction "D+_D+") (pintype "bidirectional"))
    )
    (net (code "41") (name "Net-(JP1-Pad5)") (class "Default")
      (node (ref "JP1") (pin "5") (pinfunction "5_5") (pintype "passive"))
      (node (ref "JP7") (pin "5") (pinfunction "5_5") (pintype "passive"))
      (node (ref "U$1") (pin "28") (pinfunction "28_28") (pintype "bidirectional"))
    )
    (net (code "42") (name "Net-(JP1-Pad6)") (class "Default")
      (node (ref "JP1") (pin "6") (pinfunction "6_6") (pintype "passive"))
      (node (ref "JP7") (pin "6") (pinfunction "6_6") (pintype "passive"))
      (node (ref "U$1") (pin "27") (pinfunction "27_27") (pintype "bidirectional"))
    )
    (net (code "43") (name "Net-(JP1-Pad7)") (class "Default")
      (node (ref "JP1") (pin "7") (pinfunction "7_7") (pintype "passive"))
      (node (ref "JP7") (pin "7") (pinfunction "7_7") (pintype "passive"))
      (node (ref "U$1") (pin "26") (pinfunction "26_26") (pintype "bidirectional"))
    )
    (net (code "44") (name "Net-(JP1-Pad8)") (class "Default")
      (node (ref "JP1") (pin "8") (pinfunction "8_8") (pintype "passive"))
      (node (ref "JP7") (pin "8") (pinfunction "8_8") (pintype "passive"))
      (node (ref "U$1") (pin "25") (pinfunction "25_25") (pintype "bidirectional"))
    )
    (net (code "45") (name "Net-(JP1-Pad9)") (class "Default")
      (node (ref "JP1") (pin "9") (pinfunction "9_9") (pintype "passive"))
      (node (ref "JP7") (pin "9") (pinfunction "9_9") (pintype "passive"))
      (node (ref "U$1") (pin "24") (pinfunction "24_24") (pintype "bidirectional"))
    )
    (net (code "46") (name "Net-(JP2-Pad4)") (class "Default")
      (node (ref "JP2") (pin "4") (pinfunction "4_4") (pintype "passive"))
      (node (ref "JP8") (pin "4") (pinfunction "4_4") (pintype "passive"))
      (node (ref "U$1") (pin "43") (pinfunction "43_43") (pintype "bidirectional"))
    )
    (net (code "47") (name "Net-(JP2-Pad5)") (class "Default")
      (node (ref "JP2") (pin "5") (pinfunction "5_5") (pintype "passive"))
      (node (ref "JP8") (pin "5") (pinfunction "5_5") (pintype "passive"))
      (node (ref "U$1") (pin "42") (pinfunction "42_42") (pintype "bidirectional"))
    )
    (net (code "48") (name "Net-(JP2-Pad6)") (class "Default")
      (node (ref "JP2") (pin "6") (pinfunction "6_6") (pintype "passive"))
      (node (ref "JP8") (pin "6") (pinfunction "6_6") (pintype "passive"))
      (node (ref "U$1") (pin "41") (pinfunction "41_41") (pintype "bidirectional"))
    )
    (net (code "49") (name "Net-(JP2-Pad7)") (class "Default")
      (node (ref "JP2") (pin "7") (pinfunction "7_7") (pintype "passive"))
      (node (ref "JP8") (pin "7") (pinfunction "7_7") (pintype "passive"))
      (node (ref "U$1") (pin "40") (pinfunction "40_40") (pintype "bidirectional"))
    )
    (net (code "50") (name "Net-(JP2-Pad8)") (class "Default")
      (node (ref "JP2") (pin "8") (pinfunction "8_8") (pintype "passive"))
      (node (ref "JP8") (pin "8") (pinfunction "8_8") (pintype "passive"))
      (node (ref "U$1") (pin "DO") (pinfunction "DO_DO") (pintype "bidirectional"))
    )
    (net (code "51") (name "Net-(JP2-Pad9)") (class "Default")
      (node (ref "JP2") (pin "9") (pinfunction "9_9") (pintype "passive"))
      (node (ref "JP8") (pin "9") (pinfunction "9_9") (pintype "passive"))
      (node (ref "U$1") (pin "DC") (pinfunction "DC_DC") (pintype "bidirectional"))
    )
    (net (code "52") (name "Net-(JP2-Pad10)") (class "Default")
      (node (ref "JP2") (pin "10") (pinfunction "10_10") (pintype "passive"))
      (node (ref "JP8") (pin "10") (pinfunction "10_10") (pintype "passive"))
      (node (ref "U$1") (pin "DE") (pinfunction "DE_DE") (pintype "bidirectional"))
    )
    (net (code "53") (name "Net-(JP5-Pad1)") (class "Default")
      (node (ref "JP5") (pin "1") (pinfunction "1_1") (pintype "passive"))
      (node (ref "JP9") (pin "1") (pinfunction "1_1") (pintype "passive"))
      (node (ref "U$1") (pin "VUSB") (pinfunction "VUSB_VUSB") (pintype "power_in"))
      (node (ref "µUSB") (pin "1") (pinfunction "1_1") (pintype "passive"))
    )
    (net (code "54") (name "Net-(JP5-Pad2)") (class "Default")
      (node (ref "JP5") (pin "2") (pinfunction "2_2") (pintype "passive"))
      (node (ref "JP9") (pin "2") (pinfunction "2_2") (pintype "passive"))
      (node (ref "U$1") (pin "AREF") (pinfunction "AREF_AREF") (pintype "power_in"))
    )
    (net (code "55") (name "Net-(JP5-Pad3)") (class "Default")
      (node (ref "JP5") (pin "3") (pinfunction "3_3") (pintype "passive"))
      (node (ref "JP9") (pin "3") (pinfunction "3_3") (pintype "passive"))
      (node (ref "U$1") (pin "A10") (pinfunction "A10_A10") (pintype "bidirectional"))
    )
    (net (code "56") (name "Net-(JP5-Pad4)") (class "Default")
      (node (ref "JP5") (pin "4") (pinfunction "4_4") (pintype "passive"))
      (node (ref "JP9") (pin "4") (pinfunction "4_4") (pintype "passive"))
      (node (ref "U$1") (pin "A11") (pinfunction "A11_A11") (pintype "bidirectional"))
    )
    (net (code "57") (name "Net-(JP10-Pad1)") (class "Default")
      (node (ref "JP10") (pin "1") (pinfunction "1_1") (pintype "passive"))
      (node (ref "JP3") (pin "1") (pinfunction "1_1") (pintype "passive"))
      (node (ref "U$1") (pin "VIN") (pinfunction "VIN_VIN") (pintype "power_in"))
    )
    (net (code "58") (name "Net-(JP10-Pad2)") (class "Default")
      (node (ref "JP10") (pin "2") (pinfunction "2_2") (pintype "passive"))
      (node (ref "JP3") (pin "2") (pinfunction "2_2") (pintype "passive"))
      (node (ref "U$1") (pin "AGND") (pinfunction "AGND_AGND") (pintype "power_in"))
    )
    (net (code "59") (name "Net-(JP10-Pad18)") (class "Default")
      (node (ref "JP10") (pin "18") (pinfunction "18_18") (pintype "passive"))
      (node (ref "JP3") (pin "18") (pinfunction "18_18") (pintype "passive"))
      (node (ref "U$1") (pin "39/A20") (pinfunction "39/A20_39/A20") (pintype "bidirectional"))
    )
    (net (code "60") (name "Net-(JP11-Pad3)") (class "Default")
      (node (ref "JP11") (pin "3") (pinfunction "3_3") (pintype "passive"))
      (node (ref "JP4") (pin "3") (pinfunction "3_3") (pintype "passive"))
      (node (ref "U$1") (pin "55") (pinfunction "55_55") (pintype "bidirectional"))
    )
    (net (code "61") (name "Net-(JP11-Pad4)") (class "Default")
      (node (ref "JP11") (pin "4") (pinfunction "4_4") (pintype "passive"))
      (node (ref "JP4") (pin "4") (pinfunction "4_4") (pintype "passive"))
      (node (ref "U$1") (pin "54") (pinfunction "54_54") (pintype "bidirectional"))
    )
    (net (code "62") (name "Net-(JP11-Pad5)") (class "Default")
      (node (ref "JP11") (pin "5") (pinfunction "5_5") (pintype "passive"))
      (node (ref "JP4") (pin "5") (pinfunction "5_5") (pintype "passive"))
      (node (ref "U$1") (pin "53") (pinfunction "53_53") (pintype "bidirectional"))
    )
    (net (code "63") (name "Net-(JP11-Pad6)") (class "Default")
      (node (ref "JP11") (pin "6") (pinfunction "6_6") (pintype "passive"))
      (node (ref "JP4") (pin "6") (pinfunction "6_6") (pintype "passive"))
      (node (ref "U$1") (pin "52") (pinfunction "52_52") (pintype "bidirectional"))
    )
    (net (code "64") (name "Net-(JP11-Pad7)") (class "Default")
      (node (ref "JP11") (pin "7") (pinfunction "7_7") (pintype "passive"))
      (node (ref "JP4") (pin "7") (pinfunction "7_7") (pintype "passive"))
      (node (ref "U$1") (pin "51") (pinfunction "51_51") (pintype "bidirectional"))
    )
    (net (code "65") (name "Net-(JP12-Pad1)") (class "Default")
      (node (ref "JP12") (pin "1") (pinfunction "1_1") (pintype "passive"))
      (node (ref "JP6") (pin "1") (pinfunction "1_1") (pintype "passive"))
      (node (ref "U$1") (pin "VBAT") (pinfunction "VBAT_VBAT") (pintype "power_in"))
    )
    (net (code "66") (name "Net-(JP12-Pad2)") (class "Default")
      (node (ref "JP12") (pin "2") (pinfunction "2_2") (pintype "passive"))
      (node (ref "JP6") (pin "2") (pinfunction "2_2") (pintype "passive"))
      (node (ref "U$1") (pin "PGM") (pinfunction "PGM_PGM") (pintype "bidirectional"))
    )
    (net (code "67") (name "Net-(JP12-Pad3)") (class "Default")
      (node (ref "JP12") (pin "3") (pinfunction "3_3") (pintype "passive"))
      (node (ref "JP6") (pin "3") (pinfunction "3_3") (pintype "passive"))
      (node (ref "U$1") (pin "RESET") (pinfunction "RESET_RESET") (pintype "bidirectional"))
    )
    (net (code "68") (name "Net-(JP13-Pad1)") (class "Default")
      (node (ref "JP13") (pin "1") (pinfunction "1_1") (pintype "passive"))
      (node (ref "U$4") (pin "INT") (pinfunction "INT_INT") (pintype "bidirectional"))
    )
    (net (code "69") (name "Net-(U$1-16{slash}A2{slash}T{slash}PWM)") (class "Default")
      (node (ref "JP10") (pin "11") (pinfunction "11_11") (pintype "passive"))
      (node (ref "JP3") (pin "11") (pinfunction "11_11") (pintype "passive"))
      (node (ref "U$1") (pin "16/A2") (pinfunction "16/A2/T/PWM_16/A2") (pintype "bidirectional"))
    )
    (net (code "70") (name "Net-(U$1-29{slash}T{slash}PWM)") (class "Default")
      (node (ref "JP1") (pin "4") (pinfunction "4_4") (pintype "passive"))
      (node (ref "JP7") (pin "4") (pinfunction "4_4") (pintype "passive"))
      (node (ref "U$1") (pin "29") (pinfunction "29/T/PWM_29") (pintype "bidirectional"))
    )
    (net (code "71") (name "Net-(U$1-30{slash}T{slash}PWM)") (class "Default")
      (node (ref "JP1") (pin "3") (pinfunction "3_3") (pintype "passive"))
      (node (ref "JP7") (pin "3") (pinfunction "3_3") (pintype "passive"))
      (node (ref "U$1") (pin "30") (pinfunction "30/T/PWM_30") (pintype "bidirectional"))
    )
    (net (code "72") (name "Net-(U$1-31{slash}A12{slash}RX4)") (class "Default")
      (node (ref "JP1") (pin "2") (pinfunction "2_2") (pintype "passive"))
      (node (ref "JP7") (pin "2") (pinfunction "2_2") (pintype "passive"))
      (node (ref "U$1") (pin "31/A12") (pinfunction "31/A12/RX4_31/A12") (pintype "bidirectional"))
    )
    (net (code "73") (name "Net-(U$1-32{slash}A13{slash}TX4)") (class "Default")
      (node (ref "JP1") (pin "1") (pinfunction "1_1") (pintype "passive"))
      (node (ref "JP7") (pin "1") (pinfunction "1_1") (pintype "passive"))
      (node (ref "U$1") (pin "32/A13") (pinfunction "32/A13/TX4_32/A13") (pintype "bidirectional"))
    )
    (net (code "74") (name "Net-(U$1-33{slash}A14{slash}TX5{slash}CAN1-TX)") (class "Default")
      (node (ref "JP10") (pin "24") (pinfunction "24_24") (pintype "passive"))
      (node (ref "JP3") (pin "24") (pinfunction "24_24") (pintype "passive"))
      (node (ref "U$1") (pin "33/A14") (pinfunction "33/A14/TX5/CAN1-TX_33/A14") (pintype "bidirectional"))
    )
    (net (code "75") (name "Net-(U$1-34{slash}A15{slash}RX5{slash}CAN1-RX)") (class "Default")
      (node (ref "JP10") (pin "23") (pinfunction "23_23") (pintype "passive"))
      (node (ref "JP3") (pin "23") (pinfunction "23_23") (pintype "passive"))
      (node (ref "U$1") (pin "34/A15") (pinfunction "34/A15/RX5/CAN1-RX_34/A15") (pintype "bidirectional"))
    )
    (net (code "76") (name "Net-(U$1-35{slash}A16{slash}PWM)") (class "Default")
      (node (ref "JP10") (pin "22") (pinfunction "22_22") (pintype "passive"))
      (node (ref "JP3") (pin "22") (pinfunction "22_22") (pintype "passive"))
      (node (ref "U$1") (pin "35/A16") (pinfunction "35/A16/PWM_35/A16") (pintype "bidirectional"))
    )
    (net (code "77") (name "Net-(U$1-36{slash}A17{slash}PWM)") (class "Default")
      (node (ref "JP10") (pin "21") (pinfunction "21_21") (pintype "passive"))
      (node (ref "JP3") (pin "21") (pinfunction "21_21") (pintype "passive"))
      (node (ref "U$1") (pin "36/A17") (pinfunction "36/A17/PWM_36/A17") (pintype "bidirectional"))
    )
    (net (code "78") (name "Net-(U$1-37{slash}A18{slash}SCL1{slash}PWM)") (class "Default")
      (node (ref "JP10") (pin "20") (pinfunction "20_20") (pintype "passive"))
      (node (ref "JP3") (pin "20") (pinfunction "20_20") (pintype "passive"))
      (node (ref "U$1") (pin "37/A18") (pinfunction "37/A18/SCL1/PWM_37/A18") (pintype "bidirectional"))
    )
    (net (code "79") (name "Net-(U$1-38{slash}A19{slash}SDA1{slash}PWM)") (class "Default")
      (node (ref "JP10") (pin "19") (pinfunction "19_19") (pintype "passive"))
      (node (ref "JP3") (pin "19") (pinfunction "19_19") (pintype "passive"))
      (node (ref "U$1") (pin "38/A19") (pinfunction "38/A19/SDA1/PWM_38/A19") (pintype "bidirectional"))
    )
    (net (code "80") (name "Net-(U$1-A21{slash}DAC0)") (class "Default")
      (node (ref "JP10") (pin "17") (pinfunction "17_17") (pintype "passive"))
      (node (ref "JP3") (pin "17") (pinfunction "17_17") (pintype "passive"))
      (node (ref "U$1") (pin "A21") (pinfunction "A21/DAC0_A21") (pintype "bidirectional"))
    )
    (net (code "81") (name "Net-(U$1-A22{slash}DAC1)") (class "Default")
      (node (ref "JP10") (pin "16") (pinfunction "16_16") (pintype "passive"))
      (node (ref "JP3") (pin "16") (pinfunction "16_16") (pintype "passive"))
      (node (ref "U$1") (pin "A22") (pinfunction "A22/DAC1_A22") (pintype "bidirectional"))
    )
    (net (code "82") (name "Net-(U$1-A23{slash}49)") (class "Default")
      (node (ref "JP11") (pin "9") (pinfunction "9_9") (pintype "passive"))
      (node (ref "JP4") (pin "9") (pinfunction "9_9") (pintype "passive"))
      (node (ref "U$1") (pin "49") (pinfunction "A23/49_49") (pintype "bidirectional"))
    )
    (net (code "83") (name "Net-(U$1-A24{slash}50)") (class "Default")
      (node (ref "JP11") (pin "8") (pinfunction "8_8") (pintype "passive"))
      (node (ref "JP4") (pin "8") (pinfunction "8_8") (pintype "passive"))
      (node (ref "U$1") (pin "50") (pinfunction "A24/50_50") (pintype "bidirectional"))
    )
    (net (code "84") (name "Net-(U$1-MISO2{slash}45)") (class "Default")
      (node (ref "JP2") (pin "2") (pinfunction "2_2") (pintype "passive"))
      (node (ref "JP8") (pin "2") (pinfunction "2_2") (pintype "passive"))
      (node (ref "U$1") (pin "45") (pinfunction "MISO2/45_45") (pintype "bidirectional"))
    )
    (net (code "85") (name "Net-(U$1-MOSI2{slash}44)") (class "Default")
      (node (ref "JP2") (pin "3") (pinfunction "3_3") (pintype "passive"))
      (node (ref "JP8") (pin "3") (pinfunction "3_3") (pintype "passive"))
      (node (ref "U$1") (pin "44") (pinfunction "MOSI2/44_44") (pintype "bidirectional"))
    )
    (net (code "86") (name "Net-(U$1-PadUSBD+)") (class "Default")
      (node (ref "U$1") (pin "USBD+") (pinfunction "USBD+_USBD+") (pintype "bidirectional"))
      (node (ref "µUSB") (pin "2") (pinfunction "2_2") (pintype "passive"))
    )
    (net (code "87") (name "Net-(U$1-PadUSBD-)") (class "Default")
      (node (ref "U$1") (pin "USBD-") (pinfunction "USBD-_USBD-") (pintype "bidirectional"))
      (node (ref "µUSB") (pin "3") (pinfunction "3_3") (pintype "passive"))
    )
    (net (code "88") (name "Net-(U$1-RX6{slash}47)") (class "Default")
      (node (ref "JP11") (pin "11") (pinfunction "11_11") (pintype "passive"))
      (node (ref "JP4") (pin "11") (pinfunction "11_11") (pintype "passive"))
      (node (ref "U$1") (pin "47") (pinfunction "RX6/47_47") (pintype "bidirectional"))
    )
    (net (code "89") (name "Net-(U$1-SCK2{slash}46)") (class "Default")
      (node (ref "JP2") (pin "1") (pinfunction "1_1") (pintype "passive"))
      (node (ref "JP8") (pin "1") (pinfunction "1_1") (pintype "passive"))
      (node (ref "U$1") (pin "46") (pinfunction "SCK2/46_46") (pintype "bidirectional"))
    )
    (net (code "90") (name "Net-(U$1-SCL3{slash}57)") (class "Default")
      (node (ref "JP11") (pin "1") (pinfunction "1_1") (pintype "passive"))
      (node (ref "JP4") (pin "1") (pinfunction "1_1") (pintype "passive"))
      (node (ref "U$1") (pin "57") (pinfunction "SCL3/57_57") (pintype "bidirectional"))
    )
    (net (code "91") (name "Net-(U$1-SDA3{slash}56)") (class "Default")
      (node (ref "JP11") (pin "2") (pinfunction "2_2") (pintype "passive"))
      (node (ref "JP4") (pin "2") (pinfunction "2_2") (pintype "passive"))
      (node (ref "U$1") (pin "56") (pinfunction "SDA3/56_56") (pintype "bidirectional"))
    )
    (net (code "92") (name "Net-(U$1-TX6{slash}48)") (class "Default")
      (node (ref "JP11") (pin "10") (pinfunction "10_10") (pintype "passive"))
      (node (ref "JP4") (pin "10") (pinfunction "10_10") (pintype "passive"))
      (node (ref "U$1") (pin "48") (pinfunction "TX6/48_48") (pintype "bidirectional"))
    )
    (net (code "93") (name "Net-(U$2-PadRXI-1)") (class "Default")
      (node (ref "U$2") (pin "RXI-1") (pinfunction "RXI-1_RXI-1") (pintype "bidirectional"))
      (node (ref "U$2") (pin "TXO-1") (pinfunction "TXO-1_TXO-1") (pintype "bidirectional"))
      (node (ref "U$3") (pin "DATA") (pinfunction "DATA_DATA") (pintype "bidirectional"))
      (node (ref "U$6") (pin "DATA") (pinfunction "DATA_DATA") (pintype "bidirectional"))
    )
    (net (code "94") (name "Net-(U$5-A+)") (class "Default")
      (node (ref "U$5") (pin "A") (pinfunction "A+_A") (pintype "passive"))
      (node (ref "X3") (pin "2") (pinfunction "KL_2") (pintype "passive"))
    )
    (net (code "95") (name "V+") (class "Default")
      (node (ref "C10") (pin "+") (pinfunction "+_+") (pintype "passive"))
      (node (ref "C12") (pin "+") (pinfunction "+_+") (pintype "passive"))
      (node (ref "C14") (pin "+") (pinfunction "+_+") (pintype "passive"))
      (node (ref "C17") (pin "+") (pinfunction "+_+") (pintype "passive"))
      (node (ref "C4") (pin "+") (pinfunction "+_+") (pintype "passive"))
      (node (ref "C5") (pin "+") (pinfunction "+_+") (pintype "passive"))
      (node (ref "C8") (pin "+") (pinfunction "+_+") (pintype "passive"))
      (node (ref "C9") (pin "+") (pinfunction "+_+") (pintype "passive"))
      (node (ref "DC1") (pin "1") (pinfunction "VIN_1") (pintype "passive"))
      (node (ref "DC2") (pin "1") (pinfunction "VIN_1") (pintype "passive"))
      (node (ref "DC3") (pin "1") (pinfunction "VIN_1") (pintype "passive"))
      (node (ref "DC4") (pin "1") (pinfunction "VIN_1") (pintype "passive"))
      (node (ref "H1") (pin "6") (pinfunction "VS_6") (pintype "power_in"))
      (node (ref "H2") (pin "6") (pinfunction "VS_6") (pintype "power_in"))
      (node (ref "U$5") (pin "C") (pinfunction "C-_C") (pintype "passive"))
    )
    (net (code "96") (name "unconnected-(H1-SENSE-Pad8)") (class "Default")
      (node (ref "H1") (pin "8") (pinfunction "SENSE_8") (pintype "output"))
    )
    (net (code "97") (name "unconnected-(H1-THERMAL-Pad9)") (class "Default")
      (node (ref "H1") (pin "9") (pinfunction "THERMAL_9") (pintype "output"))
    )
    (net (code "98") (name "unconnected-(H2-SENSE-Pad8)") (class "Default")
      (node (ref "H2") (pin "8") (pinfunction "SENSE_8") (pintype "output"))
    )
    (net (code "99") (name "unconnected-(H2-THERMAL-Pad9)") (class "Default")
      (node (ref "H2") (pin "9") (pinfunction "THERMAL_9") (pintype "output"))
    )
    (net (code "100") (name "unconnected-(S1-S-Pad3)") (class "Default")
      (node (ref "S1") (pin "3") (pinfunction "S_3") (pintype "passive"))
    )
    (net (code "101") (name "unconnected-(U$2-PadRXI-2)") (class "Default")
      (node (ref "U$2") (pin "RXI-2") (pinfunction "RXI-2_RXI-2") (pintype "bidirectional"))
    )
    (net (code "102") (name "unconnected-(U$2-PadRXO-2)") (class "Default")
      (node (ref "U$2") (pin "RXO-2") (pinfunction "RXO-2_RXO-2") (pintype "bidirectional"))
    )
    (net (code "103") (name "unconnected-(U$2-PadTXI-2)") (class "Default")
      (node (ref "U$2") (pin "TXI-2") (pinfunction "TXI-2_TXI-2") (pintype "bidirectional"))
    )
    (net (code "104") (name "unconnected-(U$2-PadTXO-2)") (class "Default")
      (node (ref "U$2") (pin "TXO-2") (pinfunction "TXO-2_TXO-2") (pintype "bidirectional"))
    )
  )
)
